# FPGA_CONFIG.net
KiCad netlist of a schematic drawn in Altium Designer
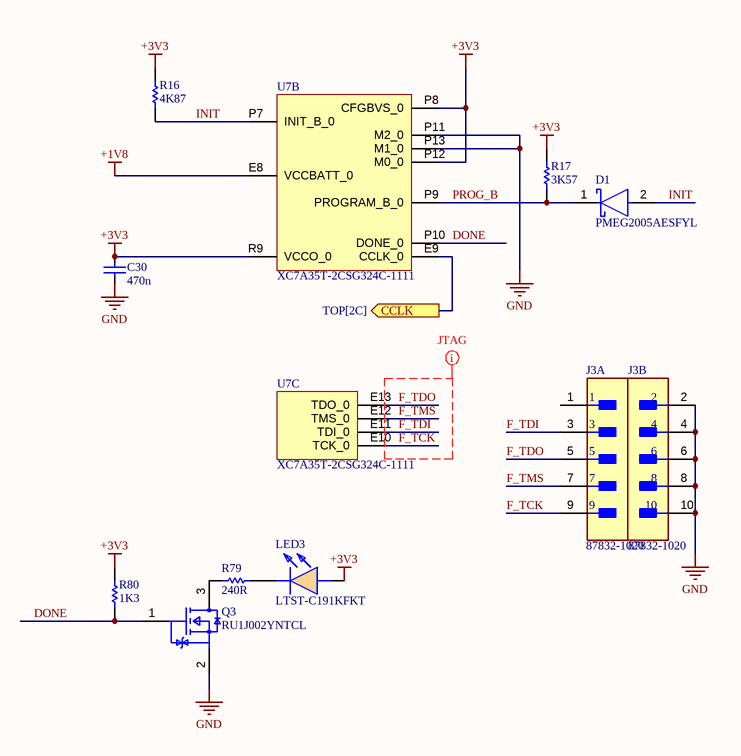
[diagram p0: FPGA CONFIG.SchDoc]

(export (version "E")
  (design (tool "Eeschema 10.0.6"))
  (components
    (comp (ref "C30")
      (value "470n")
      (footprint "pcblib1:FP-C1005-050-0_05-IPC_C")
      (description "Multilayer Ceramic Capacitors 470nF ±10% 25V X5R SMD 0402")
      (fields (field (name "VOLTAGE") "25V") (field (name "TOLERANCE") "10%"))
      (libsource (lib "Schlib1") (part "C1005X5R1E474K050BB"))
    )
    (comp (ref "D1")
      (value "PMEG2005AESFYL")
      (footprint "FP-PMEG2005AESFYL-MFG")
      (description "DIODE SCHOTTKY 20V 0.5A SOD962")
      (fields
        (field (name "OCTOPART") "https://octopart.com/pmeg2005aesfyl-nexperia-78741393")
        (field (name "MANUFACTURER") "Nexperia")
      )
      (libsource (lib "Schlib1") (part "PMEG2005AESFYL"))
    )
    (comp (ref "J3")
      (value "87832-1020")
      (footprint "FP-87832-1020-MFG")
      (description "CONN HEADER SMD 10POS 2MM")
      (libsource (lib "Altium Content Vault") (part "544f42128f4185dcb88ce1ce9bf1982"))
    )
    (comp (ref "LED3")
      (value "LTST-C191KFKT")
      (footprint "LEDC1608X55N")
      (description "LED")
      (fields (field (name "MOUSER PART NUMBER") "859-LTST-C191KFKT") (field (name "MANUFACTURER") "Lite-On"))
      (libsource (lib "Schlib1") (part "LTST-C191KFKT"))
    )
    (comp (ref "Q3")
      (value "RU1J002YNTCL")
      (footprint "FP-UMT3F-MFG")
      (description "MOSFET N-CH 50V 0.2A UMT3F")
      (fields
        (field (name "MANUFACTURER") "Rohm")
        (field (name "OCTOPART") "https://octopart.com/ru1j002yntcl-rohm-47197697")
      )
      (libsource (lib "Schlib1") (part "RU1J002YNTCL"))
    )
    (comp (ref "R16")
      (value "4K87")
      (footprint "RESC1005X40X25LL05T10")
      (fields (field (name "PART NUMBER") "RC0402FR-074K87L") (field (name "MANUFACTURER") "Yageo / Phycomp"))
      (libsource (lib "Schlib1") (part "RC0402FR-074K87L"))
    )
    (comp (ref "R17")
      (value "3K57")
      (footprint "pcblib1:RESC1005X40X25LL05T10")
      (fields (field (name "PART NUMBER") "RC0402FR-073K57L") (field (name "MANUFACTURER") "Yageo"))
      (libsource (lib "Schlib1") (part "RC0402FR-073K57L"))
    )
    (comp (ref "R79")
      (value "240R")
      (footprint "pcblib1:RESC1005X40X25LL05T10")
      (description "240R 0.063W 1% 0402 (1005 Metric)  SMD")
      (fields (field (name "POWER") "0.063 W") (field (name "TOLERANCE") "1 %"))
      (libsource (lib "Schlib1") (part "RC0402FR-07240RL"))
    )
    (comp (ref "R80")
      (value "1K3")
      (footprint "RESC1005X40X25LL05T10")
      (fields (field (name "MANUFACTURER") "Yageo / Phycomp") (field (name "PART NUMBER") "RC0402FR-071K3L"))
      (libsource (lib "Schlib1") (part "RC0402FR-071K3L"))
    )
    (comp (ref "U7")
      (value "XC7A35T-2CSG324C-1111")
      (footprint "PCBLIB1:BGA324C80P18X18_1500X1500X150")
      (description "Integrated Circuit")
      (fields
        (field (name "MANUFACTURER_PART_NUMBER") "XC7A35T-2CSG324C")
        (field (name "MOUSER PART NUMBER") "217-XC7A35T-2CSG324C")
      )
      (libsource (lib "Schlib1") (part "XC7A35T-2CSG324C-1111"))
    )
  )
  (nets
    (net (code "1") (name "+1V8") (class "Default")
      (node (ref "U7") (pin "E8") (pinfunction "VCCBATT_0_E8") (pintype "passive"))
    )
    (net (code "2") (name "+3V3") (class "Default")
      (node (ref "C30") (pin "1") (pinfunction "1_1") (pintype "passive"))
      (node (ref "LED3") (pin "2") (pinfunction "A_2") (pintype "passive"))
      (node (ref "R16") (pin "2") (pinfunction "2_2") (pintype "passive"))
      (node (ref "R17") (pin "1") (pinfunction "1_1") (pintype "passive"))
      (node (ref "R80") (pin "2") (pinfunction "2_2") (pintype "passive"))
      (node (ref "U7") (pin "P12") (pinfunction "M0_0_P12") (pintype "passive"))
      (node (ref "U7") (pin "P8") (pinfunction "CFGBVS_0_P8") (pintype "passive"))
      (node (ref "U7") (pin "R9") (pinfunction "VCCO_0_R9") (pintype "passive"))
    )
    (net (code "3") (name "/CCLK") (class "Default")
      (node (ref "U7") (pin "E9") (pinfunction "CCLK_0_E9") (pintype "passive"))
    )
    (net (code "4") (name "/DONE") (class "Default")
      (node (ref "Q3") (pin "1") (pinfunction "G_1") (pintype "passive"))
      (node (ref "R80") (pin "1") (pinfunction "1_1") (pintype "passive"))
      (node (ref "U7") (pin "P10") (pinfunction "DONE_0_P10") (pintype "passive"))
    )
    (net (code "5") (name "/F_TCK") (class "Default")
      (node (ref "J3") (pin "9") (pinfunction "9_9") (pintype "passive"))
      (node (ref "U7") (pin "E10") (pinfunction "TCK_0_E10") (pintype "passive"))
    )
    (net (code "6") (name "/F_TDI") (class "Default")
      (node (ref "J3") (pin "3") (pinfunction "3_3") (pintype "passive"))
      (node (ref "U7") (pin "E11") (pinfunction "TDI_0_E11") (pintype "passive"))
    )
    (net (code "7") (name "/F_TDO") (class "Default")
      (node (ref "J3") (pin "5") (pinfunction "5_5") (pintype "passive"))
      (node (ref "U7") (pin "E13") (pinfunction "TDO_0_E13") (pintype "passive"))
    )
    (net (code "8") (name "/F_TMS") (class "Default")
      (node (ref "J3") (pin "7") (pinfunction "7_7") (pintype "passive"))
      (node (ref "U7") (pin "E12") (pinfunction "TMS_0_E12") (pintype "passive"))
    )
    (net (code "9") (name "/INIT") (class "Default")
      (node (ref "D1") (pin "2") (pinfunction "A_2") (pintype "passive"))
      (node (ref "R16") (pin "1") (pinfunction "1_1") (pintype "passive"))
      (node (ref "U7") (pin "P7") (pinfunction "INIT_B_0_P7") (pintype "passive"))
    )
    (net (code "10") (name "/PROG_B") (class "Default")
      (node (ref "D1") (pin "1") (pinfunction "K_1") (pintype "passive"))
      (node (ref "R17") (pin "2") (pinfunction "2_2") (pintype "passive"))
      (node (ref "U7") (pin "P9") (pinfunction "PROGRAM_B_0_P9") (pintype "passive"))
    )
    (net (code "11") (name "GND") (class "Default")
      (node (ref "C30") (pin "2") (pinfunction "2_2") (pintype "passive"))
      (node (ref "J3") (pin "10") (pinfunction "10_10") (pintype "passive"))
      (node (ref "J3") (pin "2") (pinfunction "2_2") (pintype "passive"))
      (node (ref "J3") (pin "4") (pinfunction "4_4") (pintype "passive"))
      (node (ref "J3") (pin "6") (pinfunction "6_6") (pintype "passive"))
      (node (ref "J3") (pin "8") (pinfunction "8_8") (pintype "passive"))
      (node (ref "Q3") (pin "2") (pinfunction "S_2") (pintype "passive"))
      (node (ref "U7") (pin "P11") (pinfunction "M2_0_P11") (pintype "passive"))
      (node (ref "U7") (pin "P13") (pinfunction "M1_0_P13") (pintype "passive"))
    )
    (net (code "12") (name "Net-(LED3-K)") (class "Default")
      (node (ref "LED3") (pin "1") (pinfunction "K_1") (pintype "passive"))
      (node (ref "R79") (pin "2") (pinfunction "2_2") (pintype "passive"))
    )
    (net (code "13") (name "Net-(Q3-D)") (class "Default")
      (node (ref "Q3") (pin "3") (pinfunction "D_3") (pintype "passive"))
      (node (ref "R79") (pin "1") (pinfunction "1_1") (pintype "passive"))
    )
    (net (code "14") (name "unconnected-(J3-Pad1)") (class "Default")
      (node (ref "J3") (pin "1") (pinfunction "1_1") (pintype "passive"))
    )
  )
)
